# TOP_pcb_redonda_fabricar.net
KiCad netlist of a schematic drawn in EAGLE
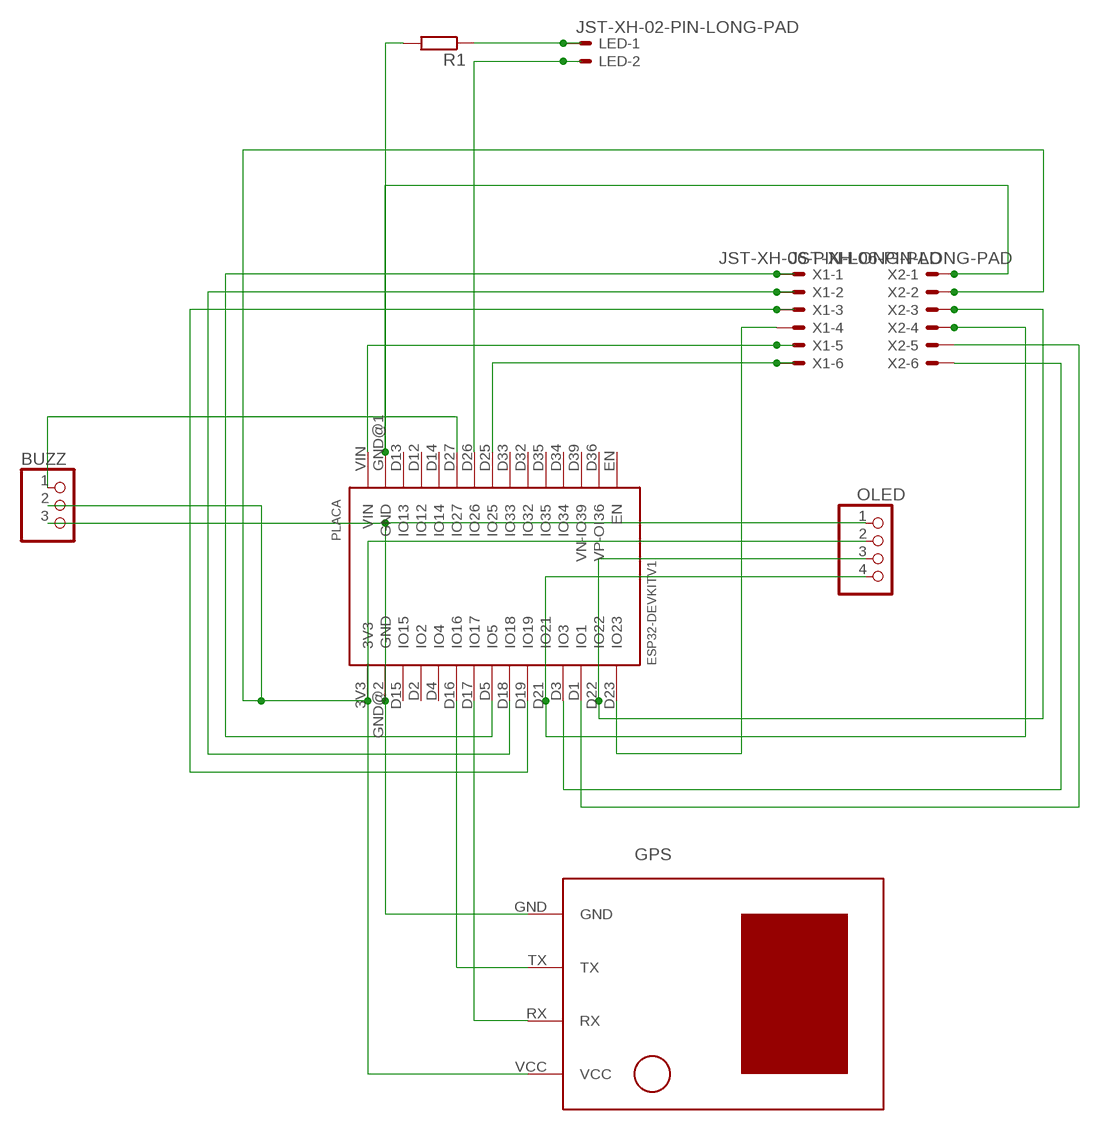
[diagram p0: schematic, sheet 1]

(export (version "E")
  (design (tool "Eeschema 10.0.6"))
  (components
    (comp (ref "BUZZ")
      (value "PINHD-1X3")
      (footprint "eagle-import:1X03")
      (libsource (lib "eagle-import") (part "PINHD-1X3"))
    )
    (comp (ref "GPS")
      (value "U-BLOX-NEO6V2")
      (footprint "eagle-import:U-BLOX-NEO6V2")
      (libsource (lib "eagle-import") (part "U-BLOX-NEO6V2"))
    )
    (comp (ref "LED")
      (value "JST-XH-02-PIN-LONG-PAD")
      (footprint "eagle-import:JST-XH-02-PACKAGE-LONG-PAD")
      (libsource (lib "eagle-import") (part "JST-XH-02-PIN-LONG-PAD"))
    )
    (comp (ref "OLED")
      (value "PINHD-1X4")
      (footprint "eagle-import:1X04")
      (libsource (lib "eagle-import") (part "PINHD-1X4"))
    )
    (comp (ref "PLACA")
      (value "ESP32DEVKITV1")
      (footprint "eagle-import:ESP32-DEVKITV1")
      (libsource (lib "eagle-import") (part "ESP32DEVKITV1"))
    )
    (comp (ref "R1")
      (value "R-EU_0207/10")
      (footprint "eagle-import:0207_10")
      (libsource (lib "eagle-import") (part "R-EU_0207/10"))
    )
    (comp (ref "X1")
      (value "JST-XH-06-PIN-LONG-PAD")
      (footprint "eagle-import:JST-XH-06-PACKAGE-LONG-PAD")
      (libsource (lib "eagle-import") (part "JST-XH-06-PIN-LONG-PAD"))
    )
    (comp (ref "X2")
      (value "JST-XH-06-PIN-LONG-PAD")
      (footprint "eagle-import:JST-XH-06-PACKAGE-LONG-PAD")
      (libsource (lib "eagle-import") (part "JST-XH-06-PIN-LONG-PAD"))
    )
  )
  (nets
    (net (code "1") (name "/GPS") (class "Default")
      (node (ref "BUZZ") (pin "3") (pinfunction "3_3") (pintype "passive"))
      (node (ref "GPS") (pin "GND") (pinfunction "GND_GND") (pintype "bidirectional"))
      (node (ref "OLED") (pin "1") (pinfunction "1_1") (pintype "passive"))
      (node (ref "PLACA") (pin "GND@2") (pinfunction "GND_GND@2") (pintype "bidirectional"))
    )
    (net (code "2") (name "Net-(LEDA-S)") (class "Default")
      (node (ref "LED") (pin "1") (pinfunction "S_1") (pintype "passive"))
      (node (ref "R1") (pin "1") (pinfunction "1_1") (pintype "passive"))
    )
    (net (code "3") (name "Net-(LEDB-S)") (class "Default")
      (node (ref "LED") (pin "2") (pinfunction "S_2") (pintype "passive"))
      (node (ref "PLACA") (pin "D26") (pinfunction "IO26_D26") (pintype "bidirectional"))
    )
    (net (code "4") (name "Net-(PLACA-IO1)") (class "Default")
      (node (ref "PLACA") (pin "D1") (pinfunction "IO1_D1") (pintype "bidirectional"))
      (node (ref "X2") (pin "5") (pinfunction "S_5") (pintype "passive"))
    )
    (net (code "5") (name "Net-(PLACA-IO3)") (class "Default")
      (node (ref "PLACA") (pin "D3") (pinfunction "IO3_D3") (pintype "bidirectional"))
      (node (ref "X2") (pin "6") (pinfunction "S_6") (pintype "passive"))
    )
    (net (code "6") (name "Net-(PLACA-IO5)") (class "Default")
      (node (ref "PLACA") (pin "D5") (pinfunction "IO5_D5") (pintype "bidirectional"))
      (node (ref "X1") (pin "1") (pinfunction "S_1") (pintype "passive"))
    )
    (net (code "7") (name "Net-(PLACA-IO16)") (class "Default")
      (node (ref "GPS") (pin "TX") (pinfunction "TX_TX") (pintype "bidirectional"))
      (node (ref "PLACA") (pin "D16") (pinfunction "IO16_D16") (pintype "bidirectional"))
    )
    (net (code "8") (name "Net-(PLACA-IO17)") (class "Default")
      (node (ref "GPS") (pin "RX") (pinfunction "RX_RX") (pintype "bidirectional"))
      (node (ref "PLACA") (pin "D17") (pinfunction "IO17_D17") (pintype "bidirectional"))
    )
    (net (code "9") (name "Net-(PLACA-IO18)") (class "Default")
      (node (ref "PLACA") (pin "D18") (pinfunction "IO18_D18") (pintype "bidirectional"))
      (node (ref "X1") (pin "2") (pinfunction "S_2") (pintype "passive"))
    )
    (net (code "10") (name "Net-(PLACA-IO19)") (class "Default")
      (node (ref "PLACA") (pin "D19") (pinfunction "IO19_D19") (pintype "bidirectional"))
      (node (ref "X1") (pin "3") (pinfunction "S_3") (pintype "passive"))
    )
    (net (code "11") (name "Net-(PLACA-IO21)") (class "Default")
      (node (ref "OLED") (pin "4") (pinfunction "4_4") (pintype "passive"))
      (node (ref "PLACA") (pin "D21") (pinfunction "IO21_D21") (pintype "bidirectional"))
      (node (ref "X2") (pin "4") (pinfunction "S_4") (pintype "passive"))
    )
    (net (code "12") (name "Net-(PLACA-IO22)") (class "Default")
      (node (ref "OLED") (pin "3") (pinfunction "3_3") (pintype "passive"))
      (node (ref "PLACA") (pin "D22") (pinfunction "IO22_D22") (pintype "bidirectional"))
      (node (ref "X2") (pin "3") (pinfunction "S_3") (pintype "passive"))
    )
    (net (code "13") (name "Net-(PLACA-IO23)") (class "Default")
      (node (ref "PLACA") (pin "D23") (pinfunction "IO23_D23") (pintype "bidirectional"))
      (node (ref "X1") (pin "4") (pinfunction "S_4") (pintype "passive"))
    )
    (net (code "14") (name "Net-(PLACA-IO25)") (class "Default")
      (node (ref "PLACA") (pin "D25") (pinfunction "IO25_D25") (pintype "bidirectional"))
      (node (ref "X1") (pin "6") (pinfunction "S_6") (pintype "passive"))
    )
    (net (code "15") (name "Net-(PLACA-IO27)") (class "Default")
      (node (ref "BUZZ") (pin "1") (pinfunction "1_1") (pintype "passive"))
      (node (ref "PLACA") (pin "D27") (pinfunction "IO27_D27") (pintype "bidirectional"))
    )
    (net (code "16") (name "Net-(X1E-S)") (class "Default")
      (node (ref "PLACA") (pin "VIN") (pinfunction "VIN_VIN") (pintype "bidirectional"))
      (node (ref "X1") (pin "5") (pinfunction "S_5") (pintype "passive"))
    )
    (net (code "17") (name "Net-(X2A-S)") (class "Default")
      (node (ref "PLACA") (pin "GND@1") (pinfunction "GND_GND@1") (pintype "bidirectional"))
      (node (ref "R1") (pin "2") (pinfunction "2_2") (pintype "passive"))
      (node (ref "X2") (pin "1") (pinfunction "S_1") (pintype "passive"))
    )
    (net (code "18") (name "Net-(X2B-S)") (class "Default")
      (node (ref "BUZZ") (pin "2") (pinfunction "2_2") (pintype "passive"))
      (node (ref "GPS") (pin "VCC") (pinfunction "VCC_VCC") (pintype "bidirectional"))
      (node (ref "OLED") (pin "2") (pinfunction "2_2") (pintype "passive"))
      (node (ref "PLACA") (pin "3V3") (pinfunction "3V3_3V3") (pintype "bidirectional"))
      (node (ref "X2") (pin "2") (pinfunction "S_2") (pintype "passive"))
    )
    (net (code "19") (name "unconnected-(PLACA-IO2-PadD2)") (class "Default")
      (node (ref "PLACA") (pin "D2") (pinfunction "IO2_D2") (pintype "bidirectional"))
    )
    (net (code "20") (name "unconnected-(PLACA-IO4-PadD4)") (class "Default")
      (node (ref "PLACA") (pin "D4") (pinfunction "IO4_D4") (pintype "bidirectional"))
    )
    (net (code "21") (name "unconnected-(PLACA-IO12-PadD12)") (class "Default")
      (node (ref "PLACA") (pin "D12") (pinfunction "IO12_D12") (pintype "bidirectional"))
    )
    (net (code "22") (name "unconnected-(PLACA-IO13-PadD13)") (class "Default")
      (node (ref "PLACA") (pin "D13") (pinfunction "IO13_D13") (pintype "bidirectional"))
    )
    (net (code "23") (name "unconnected-(PLACA-IO14-PadD14)") (class "Default")
      (node (ref "PLACA") (pin "D14") (pinfunction "IO14_D14") (pintype "bidirectional"))
    )
    (net (code "24") (name "unconnected-(PLACA-IO15-PadD15)") (class "Default")
      (node (ref "PLACA") (pin "D15") (pinfunction "IO15_D15") (pintype "bidirectional"))
    )
    (net (code "25") (name "unconnected-(PLACA-IO32-PadD32)") (class "Default")
      (node (ref "PLACA") (pin "D32") (pinfunction "IO32_D32") (pintype "bidirectional"))
    )
    (net (code "26") (name "unconnected-(PLACA-IO33-PadD33)") (class "Default")
      (node (ref "PLACA") (pin "D33") (pinfunction "IO33_D33") (pintype "bidirectional"))
    )
    (net (code "27") (name "unconnected-(PLACA-IO34-PadD34)") (class "Default")
      (node (ref "PLACA") (pin "D34") (pinfunction "IO34_D34") (pintype "bidirectional"))
    )
    (net (code "28") (name "unconnected-(PLACA-IO35-PadD35)") (class "Default")
      (node (ref "PLACA") (pin "D35") (pinfunction "IO35_D35") (pintype "bidirectional"))
    )
    (net (code "29") (name "unconnected-(PLACA-PadEN)") (class "Default")
      (node (ref "PLACA") (pin "EN") (pinfunction "EN_EN") (pintype "bidirectional"))
    )
    (net (code "30") (name "unconnected-(PLACA-VN-IO39-PadD39)") (class "Default")
      (node (ref "PLACA") (pin "D39") (pinfunction "VN-IO39_D39") (pintype "bidirectional"))
    )
    (net (code "31") (name "unconnected-(PLACA-VP-OI36-PadD36)") (class "Default")
      (node (ref "PLACA") (pin "D36") (pinfunction "VP-OI36_D36") (pintype "bidirectional"))
    )
  )
)
